# MCU_Build.net
KiCad netlist of a schematic drawn in Altium Designer
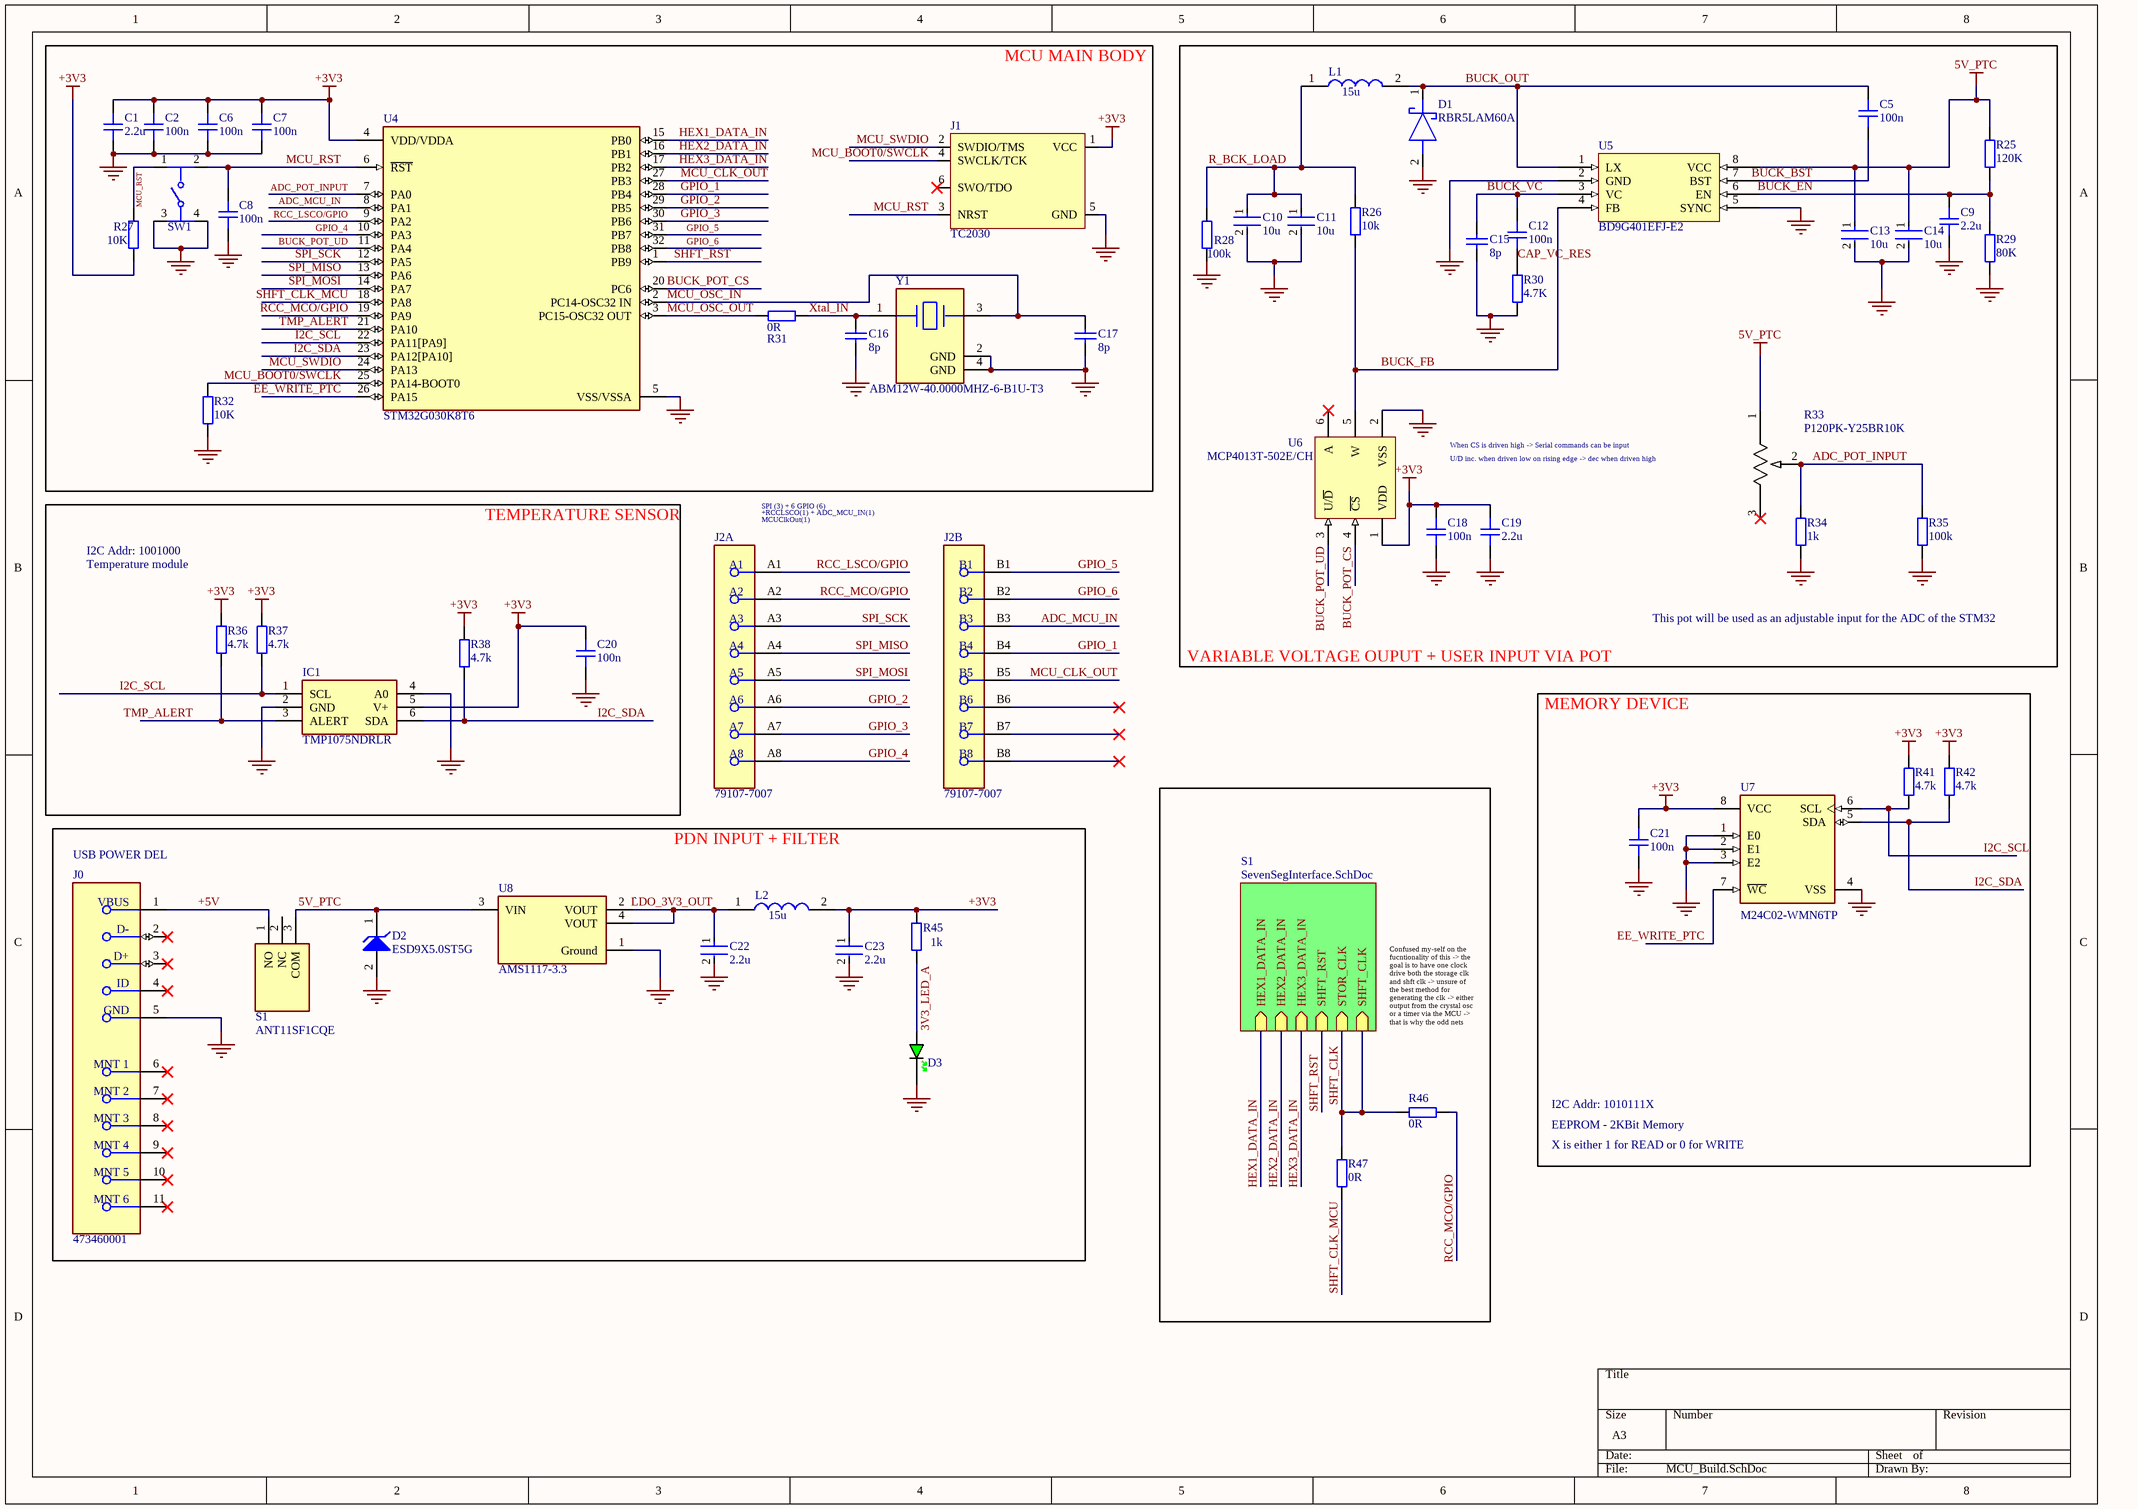
[diagram p0: MCU_Build.SchDoc]

(export (version "E")
  (design (tool "Eeschema 10.0.6"))
  (components
    (comp (ref "C1")
      (value "2.2u")
      (footprint "CAP_0603")
      (description "Capacitor SMD 0603")
      (libsource (lib "PhilsLabLib.") (part "CAP_0603"))
    )
    (comp (ref "C2")
      (value "100n")
      (footprint "CAP_0402")
      (description "Capacitor SMD 0402")
      (libsource (lib "PhilsLabLib.") (part "CAP_0402"))
    )
    (comp (ref "C5")
      (value "100n")
      (footprint "CAP_0402")
      (description "Capacitor SMD 0402")
      (libsource (lib "PhilsLabLib.") (part "CAP_0402"))
    )
    (comp (ref "C6")
      (value "100n")
      (footprint "CAP_0402")
      (description "Capacitor SMD 0402")
      (libsource (lib "PhilsLabLib.") (part "CAP_0402"))
    )
    (comp (ref "C7")
      (value "100n")
      (footprint "CAP_0402")
      (description "Capacitor SMD 0402")
      (libsource (lib "PhilsLabLib.") (part "CAP_0402"))
    )
    (comp (ref "C8")
      (value "100n")
      (footprint "CAP_0402")
      (description "Capacitor SMD 0402")
      (libsource (lib "PhilsLabLib.") (part "CAP_0402"))
    )
    (comp (ref "C9")
      (value "2.2u")
      (footprint "CAP_0603")
      (description "Capacitor SMD 0603")
      (libsource (lib "PhilsLabLib.") (part "CAP_0603"))
    )
    (comp (ref "C10")
      (value "10u")
      (footprint "FP-CL31-IPC_B")
      (description "Cap Ceramic 10uF 16V X7R ±10% SMD 1206 +125°C Embossed T/R")
      (fields (field (name "TOLERANCE") "10%"))
      (libsource (lib "Altium Content Vault") (part "b4654b650e69147ec39a6b967a45e02"))
    )
    (comp (ref "C11")
      (value "10u")
      (footprint "FP-CL31-IPC_B")
      (description "Cap Ceramic 10uF 16V X7R ±10% SMD 1206 +125°C Embossed T/R")
      (fields (field (name "TOLERANCE") "10%"))
      (libsource (lib "Altium Content Vault") (part "b4654b650e69147ec39a6b967a45e02"))
    )
    (comp (ref "C12")
      (value "100n")
      (footprint "CAP_0402")
      (description "Capacitor SMD 0402")
      (libsource (lib "PhilsLabLib.") (part "CAP_0402"))
    )
    (comp (ref "C13")
      (value "10u")
      (footprint "FP-CL31-IPC_B")
      (description "Cap Ceramic 10uF 16V X7R ±10% SMD 1206 +125°C Embossed T/R")
      (fields (field (name "TOLERANCE") "10%"))
      (libsource (lib "Altium Content Vault") (part "b4654b650e69147ec39a6b967a45e02"))
    )
    (comp (ref "C14")
      (value "10u")
      (footprint "FP-CL31-IPC_B")
      (description "Cap Ceramic 10uF 16V X7R ±10% SMD 1206 +125°C Embossed T/R")
      (fields (field (name "TOLERANCE") "10%"))
      (libsource (lib "Altium Content Vault") (part "b4654b650e69147ec39a6b967a45e02"))
    )
    (comp (ref "C15")
      (value "8p")
      (footprint "CAPC1005X55X25LL05T10")
      (fields (field (name "PART NUMBER") "GRM1555C1H8R0BA01D") (field (name "MANUFACTURER") "Murata"))
      (libsource (lib "Altium Content Vault") (part "CAP"))
    )
    (comp (ref "C16")
      (value "8p")
      (footprint "CAPC1005X55X25LL05T10")
      (fields (field (name "PART NUMBER") "GRM1555C1H8R0BA01D") (field (name "MANUFACTURER") "Murata"))
      (libsource (lib "Altium Content Vault") (part "CAP"))
    )
    (comp (ref "C17")
      (value "8p")
      (footprint "CAPC1005X55X25LL05T10")
      (fields (field (name "PART NUMBER") "GRM1555C1H8R0BA01D") (field (name "MANUFACTURER") "Murata"))
      (libsource (lib "Altium Content Vault") (part "CAP"))
    )
    (comp (ref "C18")
      (value "100n")
      (footprint "CAP_0402")
      (description "Capacitor SMD 0402")
      (libsource (lib "PhilsLabLib.") (part "CAP_0402"))
    )
    (comp (ref "C19")
      (value "2.2u")
      (footprint "CAP_0603")
      (description "Capacitor SMD 0603")
      (libsource (lib "PhilsLabLib.") (part "CAP_0603"))
    )
    (comp (ref "C20")
      (value "100n")
      (footprint "CAP_0402")
      (description "Capacitor SMD 0402")
      (libsource (lib "PhilsLabLib.") (part "CAP_0402"))
    )
    (comp (ref "C21")
      (value "100n")
      (footprint "CAP_0402")
      (description "Capacitor SMD 0402")
      (libsource (lib "PhilsLabLib.") (part "CAP_0402"))
    )
    (comp (ref "C22")
      (value "2.2u")
      (footprint "FP-CL31-IPC_B")
      (description "Cap Ceramic 10uF 16V X7R ±10% SMD 1206 +125°C Embossed T/R")
      (fields (field (name "TOLERANCE") "10%"))
      (libsource (lib "Altium Content Vault") (part "b4654b650e69147ec39a6b967a45e02"))
    )
    (comp (ref "C23")
      (value "2.2u")
      (footprint "FP-CL31-IPC_B")
      (description "Cap Ceramic 10uF 16V X7R ±10% SMD 1206 +125°C Embossed T/R")
      (fields (field (name "TOLERANCE") "10%"))
      (libsource (lib "Altium Content Vault") (part "b4654b650e69147ec39a6b967a45e02"))
    )
    (comp (ref "D1")
      (value "RBR5LAM60A")
      (footprint "SamacSys:RF071LAM4S")
      (description "Schottky Diode")
      (libsource (lib "*") (part "RBR5LAM60A"))
    )
    (comp (ref "D2")
      (value "ESD9X5.0ST5G")
      (footprint "ONSC-SOD-923-2-514AA-01_V")
      (fields (field (name "MANUFACTURER") "On Semiconductor"))
      (libsource (lib "Altium Content Vault") (part "ONSC-K1A2-2"))
    )
    (comp (ref "D3")
      (value "GREEN")
      (footprint "LED_0805_GREEN")
      (description "LED 0805 GREEN SMD")
      (libsource (lib "PhilsLabLib.") (part "LED_0805_GREEN"))
    )
    (comp (ref "IC1")
      (value "TMP1075NDRLR")
      (footprint "SamacSys:SOTFL50P160X60-6N")
      (description "Integrated Circuit")
      (fields (field (name "MOUSER PART NUMBER") "595-TMP1075NDRLR"))
      (libsource (lib "*") (part "TMP1075NDRLR"))
    )
    (comp (ref "J0")
      (value "473460001")
      (footprint "FP-473460001-MFG")
      (description "CONN RCPT USB2.0 MICRO B SMD R/A")
      (fields
        (field (name "OCTOPART") "https://octopart.com/47346-0001-molex-7164928")
        (field (name "MANUFACTURER") "Molex")
      )
      (libsource (lib "Altium Content Vault") (part "53ae1f1d9b557310b43ca686e5bb76a"))
    )
    (comp (ref "J1")
      (value "TC2030")
      (footprint "TC2030-FP")
      (description "Tag-Connect No-Solder SWD Debug Connector DO NOT PLACE")
      (fields
        (field (name "MANUFACTURER") "Tag-Connect")
        (field (name "SOURCE") "Schematic-Lib-PhilsLab.SchLib")
      )
      (libsource (lib "Combat Craft") (part "TC2030-NL"))
    )
    (comp (ref "J2")
      (value "79107-7007")
      (footprint "FP-79107-7007-MFG")
      (description "79107-7007 Conn Socket Strip RCP 16 POS 2mm Solder ST Top Entry Thru-Hole Milli-Grid™ Tube")
      (libsource (lib "Altium Content Vault") (part "e4086e6498c21784c506770357dad61"))
    )
    (comp (ref "L1")
      (value "15u")
      (footprint "SamacSys:ASPI-4030S")
      (description "Inductor")
      (fields
        (field (name "MANUFACTURER_PART_NUMBER") "ASPI-4030S-150M-T")
        (field (name "MOUSER PART NUMBER") "815-ASPI-4030S-150MT")
      )
      (libsource (lib "*") (part "ASPI-4030S-150M-T"))
    )
    (comp (ref "L2")
      (value "15u")
      (footprint "SamacSys:ASPI-4030S")
      (description "Inductor")
      (fields
        (field (name "MANUFACTURER_PART_NUMBER") "ASPI-4030S-150M-T")
        (field (name "MOUSER PART NUMBER") "815-ASPI-4030S-150MT")
      )
      (libsource (lib "*") (part "ASPI-4030S-150M-T"))
    )
    (comp (ref "R25")
      (value "120K")
      (footprint "RES_0402")
      (description "Resistor SMD 0402")
      (libsource (lib "PhilsLabLib.") (part "RES_0402"))
    )
    (comp (ref "R26")
      (value "10k")
      (footprint "RES_0402")
      (description "Resistor SMD 0402")
      (libsource (lib "PhilsLabLib.") (part "RES_0402"))
    )
    (comp (ref "R27")
      (value "10K")
      (footprint "RES_0402")
      (description "Resistor SMD 0402")
      (libsource (lib "PhilsLabLib.") (part "RES_0402"))
    )
    (comp (ref "R28")
      (value "100k")
      (footprint "RES_0402")
      (description "Resistor SMD 0402")
      (libsource (lib "PhilsLabLib.") (part "RES_0402"))
    )
    (comp (ref "R29")
      (value "80K")
      (footprint "RES_0402")
      (description "Resistor SMD 0402")
      (libsource (lib "PhilsLabLib.") (part "RES_0402"))
    )
    (comp (ref "R30")
      (value "4.7K")
      (footprint "RES_0402")
      (description "Resistor SMD 0402")
      (libsource (lib "PhilsLabLib.") (part "RES_0402"))
    )
    (comp (ref "R31")
      (value "0R")
      (footprint "RES_0402")
      (description "Resistor SMD 0402")
      (libsource (lib "PhilsLabLib.") (part "RES_0402"))
    )
    (comp (ref "R32")
      (value "10K")
      (footprint "RES_0402")
      (description "Resistor SMD 0402")
      (libsource (lib "PhilsLabLib.") (part "RES_0402"))
    )
    (comp (ref "R33")
      (value "P120PK-Y25BR10K")
      (footprint "POT_P120PK-x25_TTE")
      (description "https://www.digikey.ca/en/products/detail/tt-electronics-bi/P120PK-Y25BR10K/5957454")
      (libsource (lib "P120PK-Y25BR10K") (part "P120PK-Y25BR10K"))
    )
    (comp (ref "R34")
      (value "1k")
      (footprint "RES_0402")
      (description "Resistor SMD 0402")
      (libsource (lib "PhilsLabLib.") (part "RES_0402"))
    )
    (comp (ref "R35")
      (value "100k")
      (footprint "RES_0402")
      (description "Resistor SMD 0402")
      (libsource (lib "PhilsLabLib.") (part "RES_0402"))
    )
    (comp (ref "R36")
      (value "4.7k")
      (footprint "RES_0402")
      (description "Resistor SMD 0402")
      (libsource (lib "PhilsLabLib.") (part "RES_0402"))
    )
    (comp (ref "R37")
      (value "4.7k")
      (footprint "RES_0402")
      (description "Resistor SMD 0402")
      (libsource (lib "PhilsLabLib.") (part "RES_0402"))
    )
    (comp (ref "R38")
      (value "4.7k")
      (footprint "RES_0402")
      (description "Resistor SMD 0402")
      (libsource (lib "PhilsLabLib.") (part "RES_0402"))
    )
    (comp (ref "R41")
      (value "4.7k")
      (footprint "RES_0402")
      (description "Resistor SMD 0402")
      (libsource (lib "PhilsLabLib.") (part "RES_0402"))
    )
    (comp (ref "R42")
      (value "4.7k")
      (footprint "RES_0402")
      (description "Resistor SMD 0402")
      (libsource (lib "PhilsLabLib.") (part "RES_0402"))
    )
    (comp (ref "R45")
      (value "1k")
      (footprint "RES_0402")
      (description "Resistor SMD 0402")
      (libsource (lib "PhilsLabLib.") (part "RES_0402"))
    )
    (comp (ref "R46")
      (value "0R")
      (footprint "RES_0402")
      (description "Resistor SMD 0402")
      (libsource (lib "PhilsLabLib.") (part "RES_0402"))
    )
    (comp (ref "R47")
      (value "0R")
      (footprint "RES_0402")
      (description "Resistor SMD 0402")
      (libsource (lib "PhilsLabLib.") (part "RES_0402"))
    )
    (comp (ref "S1")
      (value "ANT11SF1CQE")
      (footprint "SamacSys:ANT11SF1CQE")
      (description "Switch")
      (libsource (lib "*") (part "ANT11SF1CQE"))
    )
    (comp (ref "SW1")
      (value "PTS810SJM250SMTRLFS")
      (footprint "FP-PTS810SJM250SMTRLFS-MFG")
      (description "SWITCH TACTILE SPST-NO 0.05A 16V")
      (libsource (lib "Altium Content Vault") (part "1adf0dd01260c80cf25a44bfd6b99ba"))
    )
    (comp (ref "U4")
      (value "STM32G030K8T6")
      (footprint "FP-LQFP32-5V-IPC_A")
      (description "IC MCU 32BIT 64KB FLASH 32LQFP")
      (libsource (lib "Altium Content Vault") (part "fea91388a178aa646681c81fcef9c35"))
    )
    (comp (ref "U5")
      (value "BD9G401EFJ-E2")
      (footprint "custom_footprints:SOIC127P600X100_HS-9N")
      (libsource (lib "custom_symbols") (part "BD9G401EFJ-E2"))
    )
    (comp (ref "U6")
      (value "MCP4013T-502E/CH")
      (footprint "SOT-23-CH6_N")
      (description "Low-Cost 64-Step Volatile Digital POT, 6-Pin SOT-23, Extended Temperature, Tape and Reel")
      (libsource (lib "Altium Content Vault") (part "IN-DPOT-MCP4012-6"))
    )
    (comp (ref "U7")
      (value "M24C02-WMN6TP")
      (footprint "FP-SO8N-SO-A-MFG")
      (description "IC EEPROM 2K I2C 400KHZ 8SO")
      (fields
        (field (name "MANUFACTURER") "STMicroelectronics")
        (field (name "OCTOPART") "https://octopart.com/m24c02-wmn6tp-stmicroelectronics-55404516")
      )
      (libsource (lib "Altium Content Vault") (part "6c91e1c1613830ec3abd94c18390ae3"))
    )
    (comp (ref "U8")
      (value "AMS1117-3.3")
      (footprint "FP-AMS1117-IPC_C")
      (description "LDO Voltage Regulators 1A, 3.3V")
      (fields
        (field (name "OCTOPART") "https://octopart.com/ams1117-3.3-advanced+monolithic+systems-25899300")
        (field (name "MANUFACTURER") "Advanced Monolithic Systems")
      )
      (libsource (lib "Altium Content Vault") (part "8bdbb5f8e77002000e30dd2845d0354"))
    )
    (comp (ref "Y1")
      (value "ABM12W-40.0000MHZ-6-B1U-T3")
      (footprint "FP-ABM12W-MFG")
      (description "Crystal 40MHz ±10ppm 6pF SMD-4 1.6mm x 1.2mm")
      (libsource (lib "Altium Content Vault") (part "7e21b6506f3e6571bf1303cf0e4723c"))
    )
  )
  (nets
    (net (code "1") (name "+3V3") (class "Default")
      (node (ref "C1") (pin "2") (pinfunction "2_2") (pintype "passive"))
      (node (ref "C18") (pin "2") (pinfunction "2_2") (pintype "passive"))
      (node (ref "C19") (pin "2") (pinfunction "2_2") (pintype "passive"))
      (node (ref "C2") (pin "2") (pinfunction "2_2") (pintype "passive"))
      (node (ref "C20") (pin "2") (pinfunction "2_2") (pintype "passive"))
      (node (ref "C21") (pin "2") (pinfunction "2_2") (pintype "passive"))
      (node (ref "C23") (pin "1") (pinfunction "1_1") (pintype "passive"))
      (node (ref "C6") (pin "2") (pinfunction "2_2") (pintype "passive"))
      (node (ref "C7") (pin "2") (pinfunction "2_2") (pintype "passive"))
      (node (ref "IC1") (pin "5") (pinfunction "V+_5") (pintype "passive"))
      (node (ref "J1") (pin "1") (pinfunction "VCC_1") (pintype "passive"))
      (node (ref "L2") (pin "2") (pinfunction "2_2") (pintype "passive"))
      (node (ref "R27") (pin "2") (pinfunction "2_2") (pintype "passive"))
      (node (ref "R36") (pin "1") (pinfunction "1_1") (pintype "passive"))
      (node (ref "R37") (pin "1") (pinfunction "1_1") (pintype "passive"))
      (node (ref "R38") (pin "1") (pinfunction "1_1") (pintype "passive"))
      (node (ref "R41") (pin "1") (pinfunction "1_1") (pintype "passive"))
      (node (ref "R42") (pin "1") (pinfunction "1_1") (pintype "passive"))
      (node (ref "R45") (pin "1") (pinfunction "1_1") (pintype "passive"))
      (node (ref "U4") (pin "4") (pinfunction "VDD/VDDA_4") (pintype "power_in"))
      (node (ref "U6") (pin "1") (pinfunction "VDD_1") (pintype "power_in"))
      (node (ref "U7") (pin "8") (pinfunction "VCC_8") (pintype "power_in"))
    )
    (net (code "2") (name "/+5V") (class "Default")
      (node (ref "J0") (pin "1") (pinfunction "VBUS_1") (pintype "power_in"))
      (node (ref "S1") (pin "1") (pinfunction "NO_1") (pintype "passive"))
    )
    (net (code "3") (name "/3V3_LED_A") (class "Default")
      (node (ref "D3") (pin "A") (pinfunction "A_A") (pintype "passive"))
      (node (ref "R45") (pin "2") (pinfunction "2_2") (pintype "passive"))
    )
    (net (code "4") (name "/ADC_MCU_IN") (class "Default")
      (node (ref "J2") (pin "B3") (pinfunction "B3_B3") (pintype "passive"))
      (node (ref "U4") (pin "8") (pinfunction "PA1_8") (pintype "bidirectional"))
    )
    (net (code "5") (name "/ADC_POT_INPUT") (class "Default")
      (node (ref "R33") (pin "2") (pinfunction "2_2") (pintype "passive"))
      (node (ref "R34") (pin "2") (pinfunction "2_2") (pintype "passive"))
      (node (ref "R35") (pin "2") (pinfunction "2_2") (pintype "passive"))
      (node (ref "U4") (pin "7") (pinfunction "PA0_7") (pintype "bidirectional"))
    )
    (net (code "6") (name "/BUCK_BST") (class "Default")
      (node (ref "C5") (pin "1") (pinfunction "1_1") (pintype "passive"))
      (node (ref "U5") (pin "7") (pinfunction "BST_7") (pintype "input"))
    )
    (net (code "7") (name "/BUCK_EN") (class "Default")
      (node (ref "C9") (pin "2") (pinfunction "2_2") (pintype "passive"))
      (node (ref "R25") (pin "1") (pinfunction "1_1") (pintype "passive"))
      (node (ref "R29") (pin "2") (pinfunction "2_2") (pintype "passive"))
      (node (ref "U5") (pin "6") (pinfunction "EN_6") (pintype "input"))
    )
    (net (code "8") (name "/BUCK_FB") (class "Default")
      (node (ref "R26") (pin "1") (pinfunction "1_1") (pintype "passive"))
      (node (ref "U5") (pin "4") (pinfunction "FB_4") (pintype "input"))
      (node (ref "U6") (pin "5") (pinfunction "W_5") (pintype "passive"))
    )
    (net (code "9") (name "/BUCK_OUT") (class "Default")
      (node (ref "C5") (pin "2") (pinfunction "2_2") (pintype "passive"))
      (node (ref "D1") (pin "1") (pinfunction "K_1") (pintype "passive"))
      (node (ref "L1") (pin "2") (pinfunction "2_2") (pintype "passive"))
      (node (ref "U5") (pin "1") (pinfunction "LX_1") (pintype "input"))
    )
    (net (code "10") (name "/BUCK_POT_CS") (class "Default")
      (node (ref "U4") (pin "20") (pinfunction "PC6_20") (pintype "bidirectional"))
      (node (ref "U6") (pin "4") (pinfunction "~{CS}_4") (pintype "input"))
    )
    (net (code "11") (name "/BUCK_POT_UD") (class "Default")
      (node (ref "U4") (pin "11") (pinfunction "PA4_11") (pintype "bidirectional"))
      (node (ref "U6") (pin "3") (pinfunction "U/~{D}_3") (pintype "input"))
    )
    (net (code "12") (name "/BUCK_VC") (class "Default")
      (node (ref "C12") (pin "2") (pinfunction "2_2") (pintype "passive"))
      (node (ref "C15") (pin "2") (pinfunction "2_2") (pintype "passive"))
      (node (ref "U5") (pin "3") (pinfunction "VC_3") (pintype "input"))
    )
    (net (code "13") (name "/CAP_VC_RES") (class "Default")
      (node (ref "C12") (pin "1") (pinfunction "1_1") (pintype "passive"))
      (node (ref "R30") (pin "2") (pinfunction "2_2") (pintype "passive"))
    )
    (net (code "14") (name "/EE_WRITE_PTC") (class "Default")
      (node (ref "U4") (pin "26") (pinfunction "PA15_26") (pintype "bidirectional"))
      (node (ref "U7") (pin "7") (pinfunction "~{WC}_7") (pintype "input"))
    )
    (net (code "15") (name "/GPIO_1") (class "Default")
      (node (ref "J2") (pin "B4") (pinfunction "B4_B4") (pintype "passive"))
      (node (ref "U4") (pin "28") (pinfunction "PB4_28") (pintype "bidirectional"))
    )
    (net (code "16") (name "/GPIO_2") (class "Default")
      (node (ref "J2") (pin "A6") (pinfunction "A6_A6") (pintype "passive"))
      (node (ref "U4") (pin "29") (pinfunction "PB5_29") (pintype "bidirectional"))
    )
    (net (code "17") (name "/GPIO_3") (class "Default")
      (node (ref "J2") (pin "A7") (pinfunction "A7_A7") (pintype "passive"))
      (node (ref "U4") (pin "30") (pinfunction "PB6_30") (pintype "bidirectional"))
    )
    (net (code "18") (name "/GPIO_4") (class "Default")
      (node (ref "J2") (pin "A8") (pinfunction "A8_A8") (pintype "passive"))
      (node (ref "U4") (pin "10") (pinfunction "PA3_10") (pintype "bidirectional"))
    )
    (net (code "19") (name "/GPIO_5") (class "Default")
      (node (ref "J2") (pin "B1") (pinfunction "B1_B1") (pintype "passive"))
      (node (ref "U4") (pin "31") (pinfunction "PB7_31") (pintype "bidirectional"))
    )
    (net (code "20") (name "/GPIO_6") (class "Default")
      (node (ref "J2") (pin "B2") (pinfunction "B2_B2") (pintype "passive"))
      (node (ref "U4") (pin "32") (pinfunction "PB8_32") (pintype "bidirectional"))
    )
    (net (code "21") (name "/HEX1_DATA_IN") (class "Default")
      (node (ref "U4") (pin "15") (pinfunction "PB0_15") (pintype "bidirectional"))
    )
    (net (code "22") (name "/HEX2_DATA_IN") (class "Default")
      (node (ref "U4") (pin "16") (pinfunction "PB1_16") (pintype "bidirectional"))
    )
    (net (code "23") (name "/HEX3_DATA_IN") (class "Default")
      (node (ref "U4") (pin "17") (pinfunction "PB2_17") (pintype "bidirectional"))
    )
    (net (code "24") (name "/I2C_SCL") (class "Default")
      (node (ref "IC1") (pin "1") (pinfunction "SCL_1") (pintype "passive"))
      (node (ref "R37") (pin "2") (pinfunction "2_2") (pintype "passive"))
      (node (ref "R41") (pin "2") (pinfunction "2_2") (pintype "passive"))
      (node (ref "U4") (pin "22") (pinfunction "PA11[PA9]_22") (pintype "bidirectional"))
      (node (ref "U7") (pin "6") (pinfunction "SCL_6") (pintype "input"))
    )
    (net (code "25") (name "/I2C_SDA") (class "Default")
      (node (ref "IC1") (pin "6") (pinfunction "SDA_6") (pintype "passive"))
      (node (ref "R38") (pin "2") (pinfunction "2_2") (pintype "passive"))
      (node (ref "R42") (pin "2") (pinfunction "2_2") (pintype "passive"))
      (node (ref "U4") (pin "23") (pinfunction "PA12[PA10]_23") (pintype "bidirectional"))
      (node (ref "U7") (pin "5") (pinfunction "SDA_5") (pintype "bidirectional"))
    )
    (net (code "26") (name "/LDO_3V3_OUT") (class "Default")
      (node (ref "C22") (pin "1") (pinfunction "1_1") (pintype "passive"))
      (node (ref "L2") (pin "1") (pinfunction "1_1") (pintype "passive"))
      (node (ref "U8") (pin "2") (pinfunction "VOUT_2") (pintype "passive"))
      (node (ref "U8") (pin "4") (pinfunction "VOUT_4") (pintype "passive"))
    )
    (net (code "27") (name "/MCU_BOOT0{slash}SWCLK") (class "Default")
      (node (ref "J1") (pin "4") (pinfunction "SWCLK/TCK_4") (pintype "passive"))
      (node (ref "R32") (pin "1") (pinfunction "1_1") (pintype "passive"))
      (node (ref "U4") (pin "25") (pinfunction "PA14-BOOT0_25") (pintype "bidirectional"))
    )
    (net (code "28") (name "/MCU_CLK_OUT") (class "Default")
      (node (ref "J2") (pin "B5") (pinfunction "B5_B5") (pintype "passive"))
      (node (ref "U4") (pin "27") (pinfunction "PB3_27") (pintype "bidirectional"))
    )
    (net (code "29") (name "/MCU_OSC_IN") (class "Default")
      (node (ref "C17") (pin "2") (pinfunction "2_2") (pintype "passive"))
      (node (ref "U4") (pin "2") (pinfunction "PC14-OSC32_IN_2") (pintype "bidirectional"))
      (node (ref "Y1") (pin "3") (pinfunction "3_3") (pintype "passive"))
    )
    (net (code "30") (name "/MCU_OSC_OUT") (class "Default")
      (node (ref "R31") (pin "2") (pinfunction "2_2") (pintype "passive"))
      (node (ref "U4") (pin "3") (pinfunction "PC15-OSC32_OUT_3") (pintype "bidirectional"))
    )
    (net (code "31") (name "/MCU_RST") (class "Default")
      (node (ref "C8") (pin "2") (pinfunction "2_2") (pintype "passive"))
      (node (ref "J1") (pin "3") (pinfunction "NRST_3") (pintype "passive"))
      (node (ref "R27") (pin "1") (pinfunction "1_1") (pintype "passive"))
      (node (ref "SW1") (pin "1") (pinfunction "1_1") (pintype "passive"))
      (node (ref "SW1") (pin "2") (pinfunction "2_2") (pintype "passive"))
      (node (ref "U4") (pin "6") (pinfunction "~{RST}_6") (pintype "input"))
    )
    (net (code "32") (name "/MCU_SWDIO") (class "Default")
      (node (ref "J1") (pin "2") (pinfunction "SWDIO/TMS_2") (pintype "passive"))
      (node (ref "U4") (pin "24") (pinfunction "PA13_24") (pintype "bidirectional"))
    )
    (net (code "33") (name "/RCC_LSCO{slash}GPIO") (class "Default")
      (node (ref "J2") (pin "A1") (pinfunction "A1_A1") (pintype "passive"))
      (node (ref "U4") (pin "9") (pinfunction "PA2_9") (pintype "bidirectional"))
    )
    (net (code "34") (name "/RCC_MCO{slash}GPIO") (class "Default")
      (node (ref "J2") (pin "A2") (pinfunction "A2_A2") (pintype "passive"))
      (node (ref "R46") (pin "1") (pinfunction "1_1") (pintype "passive"))
      (node (ref "U4") (pin "19") (pinfunction "PA9_19") (pintype "bidirectional"))
    )
    (net (code "35") (name "/R_BCK_LOAD") (class "Default")
      (node (ref "C10") (pin "1") (pinfunction "1_1") (pintype "passive"))
      (node (ref "C11") (pin "1") (pinfunction "1_1") (pintype "passive"))
      (node (ref "L1") (pin "1") (pinfunction "1_1") (pintype "passive"))
      (node (ref "R26") (pin "2") (pinfunction "2_2") (pintype "passive"))
      (node (ref "R28") (pin "2") (pinfunction "2_2") (pintype "passive"))
    )
    (net (code "36") (name "/SHFT_CLK") (class "Default")
      (node (ref "R46") (pin "2") (pinfunction "2_2") (pintype "passive"))
      (node (ref "R47") (pin "1") (pinfunction "1_1") (pintype "passive"))
    )
    (net (code "37") (name "/SHFT_CLK_MCU") (class "Default")
      (node (ref "R47") (pin "2") (pinfunction "2_2") (pintype "passive"))
      (node (ref "U4") (pin "18") (pinfunction "PA8_18") (pintype "bidirectional"))
    )
    (net (code "38") (name "/SHFT_RST") (class "Default")
      (node (ref "U4") (pin "1") (pinfunction "PB9_1") (pintype "bidirectional"))
    )
    (net (code "39") (name "/SPI_MISO") (class "Default")
      (node (ref "J2") (pin "A4") (pinfunction "A4_A4") (pintype "passive"))
      (node (ref "U4") (pin "13") (pinfunction "PA6_13") (pintype "bidirectional"))
    )
    (net (code "40") (name "/SPI_MOSI") (class "Default")
      (node (ref "J2") (pin "A5") (pinfunction "A5_A5") (pintype "passive"))
      (node (ref "U4") (pin "14") (pinfunction "PA7_14") (pintype "bidirectional"))
    )
    (net (code "41") (name "/SPI_SCK") (class "Default")
      (node (ref "J2") (pin "A3") (pinfunction "A3_A3") (pintype "passive"))
      (node (ref "U4") (pin "12") (pinfunction "PA5_12") (pintype "bidirectional"))
    )
    (net (code "42") (name "/TMP_ALERT") (class "Default")
      (node (ref "IC1") (pin "3") (pinfunction "ALERT_3") (pintype "passive"))
      (node (ref "R36") (pin "2") (pinfunction "2_2") (pintype "passive"))
      (node (ref "U4") (pin "21") (pinfunction "PA10_21") (pintype "bidirectional"))
    )
    (net (code "43") (name "/Xtal_IN") (class "Default")
      (node (ref "C16") (pin "2") (pinfunction "2_2") (pintype "passive"))
      (node (ref "R31") (pin "1") (pinfunction "1_1") (pintype "passive"))
      (node (ref "Y1") (pin "1") (pinfunction "1_1") (pintype "passive"))
    )
    (net (code "44") (name "5V_PTC") (class "Default")
      (node (ref "C13") (pin "1") (pinfunction "1_1") (pintype "passive"))
      (node (ref "C14") (pin "1") (pinfunction "1_1") (pintype "passive"))
      (node (ref "D2") (pin "1") (pinfunction "K_1") (pintype "passive"))
      (node (ref "R25") (pin "2") (pinfunction "2_2") (pintype "passive"))
      (node (ref "R33") (pin "1") (pinfunction "1_1") (pintype "passive"))
      (node (ref "S1") (pin "3") (pinfunction "COM_3") (pintype "passive"))
      (node (ref "U5") (pin "8") (pinfunction "VCC_8") (pintype "input"))
      (node (ref "U8") (pin "3") (pinfunction "VIN_3") (pintype "power_in"))
    )
    (net (code "45") (name "GND") (class "Default")
      (node (ref "C1") (pin "1") (pinfunction "1_1") (pintype "passive"))
      (node (ref "C10") (pin "2") (pinfunction "2_2") (pintype "passive"))
      (node (ref "C11") (pin "2") (pinfunction "2_2") (pintype "passive"))
      (node (ref "C13") (pin "2") (pinfunction "2_2") (pintype "passive"))
      (node (ref "C14") (pin "2") (pinfunction "2_2") (pintype "passive"))
      (node (ref "C15") (pin "1") (pinfunction "1_1") (pintype "passive"))
      (node (ref "C16") (pin "1") (pinfunction "1_1") (pintype "passive"))
      (node (ref "C17") (pin "1") (pinfunction "1_1") (pintype "passive"))
      (node (ref "C18") (pin "1") (pinfunction "1_1") (pintype "passive"))
      (node (ref "C19") (pin "1") (pinfunction "1_1") (pintype "passive"))
      (node (ref "C2") (pin "1") (pinfunction "1_1") (pintype "passive"))
      (node (ref "C20") (pin "1") (pinfunction "1_1") (pintype "passive"))
      (node (ref "C21") (pin "1") (pinfunction "1_1") (pintype "passive"))
      (node (ref "C22") (pin "2") (pinfunction "2_2") (pintype "passive"))
      (node (ref "C23") (pin "2") (pinfunction "2_2") (pintype "passive"))
      (node (ref "C6") (pin "1") (pinfunction "1_1") (pintype "passive"))
      (node (ref "C7") (pin "1") (pinfunction "1_1") (pintype "passive"))
      (node (ref "C8") (pin "1") (pinfunction "1_1") (pintype "passive"))
      (node (ref "C9") (pin "1") (pinfunction "1_1") (pintype "passive"))
      (node (ref "D1") (pin "2") (pinfunction "A_2") (pintype "passive"))
      (node (ref "D2") (pin "2") (pinfunction "A_2") (pintype "passive"))
      (node (ref "D3") (pin "K") (pinfunction "K_K") (pintype "passive"))
      (node (ref "IC1") (pin "2") (pinfunction "GND_2") (pintype "passive"))
      (node (ref "IC1") (pin "4") (pinfunction "A0_4") (pintype "passive"))
      (node (ref "J0") (pin "5") (pinfunction "GND_5") (pintype "power_in"))
      (node (ref "J1") (pin "5") (pinfunction "GND_5") (pintype "passive"))
      (node (ref "R28") (pin "1") (pinfunction "1_1") (pintype "passive"))
      (node (ref "R29") (pin "1") (pinfunction "1_1") (pintype "passive"))
      (node (ref "R30") (pin "1") (pinfunction "1_1") (pintype "passive"))
      (node (ref "R32") (pin "2") (pinfunction "2_2") (pintype "passive"))
      (node (ref "R34") (pin "1") (pinfunction "1_1") (pintype "passive"))
      (node (ref "R35") (pin "1") (pinfunction "1_1") (pintype "passive"))
      (node (ref "SW1") (pin "3") (pinfunction "3_3") (pintype "passive"))
      (node (ref "SW1") (pin "4") (pinfunction "4_4") (pintype "passive"))
      (node (ref "U4") (pin "5") (pinfunction "VSS/VSSA_5") (pintype "power_in"))
      (node (ref "U5") (pin "2") (pinfunction "GND_2") (pintype "input"))
      (node (ref "U5") (pin "5") (pinfunction "SYNC_5") (pintype "input"))
      (node (ref "U6") (pin "2") (pinfunction "VSS_2") (pintype "power_in"))
      (node (ref "U7") (pin "1") (pinfunction "E0_1") (pintype "input"))
      (node (ref "U7") (pin "2") (pinfunction "E1_2") (pintype "input"))
      (node (ref "U7") (pin "3") (pinfunction "E2_3") (pintype "input"))
      (node (ref "U7") (pin "4") (pinfunction "VSS_4") (pintype "power_in"))
      (node (ref "U8") (pin "1") (pinfunction "Ground_1") (pintype "power_in"))
      (node (ref "Y1") (pin "2") (pinfunction "GND_2") (pintype "power_in"))
      (node (ref "Y1") (pin "4") (pinfunction "GND_4") (pintype "power_in"))
    )
    (net (code "46") (name "unconnected-(J0-D+-Pad3)") (class "Default")
      (node (ref "J0") (pin "3") (pinfunction "D+_3") (pintype "bidirectional+no_connect"))
    )
    (net (code "47") (name "unconnected-(J0-D--Pad2)") (class "Default")
      (node (ref "J0") (pin "2") (pinfunction "D-_2") (pintype "bidirectional+no_connect"))
    )
    (net (code "48") (name "unconnected-(J0-ID-Pad4)") (class "Default")
      (node (ref "J0") (pin "4") (pinfunction "ID_4") (pintype "passive+no_connect"))
    )
    (net (code "49") (name "unconnected-(J0-MNT_1-Pad6)") (class "Default")
      (node (ref "J0") (pin "6") (pinfunction "MNT_1_6") (pintype "passive+no_connect"))
    )
    (net (code "50") (name "unconnected-(J0-MNT_2-Pad7)") (class "Default")
      (node (ref "J0") (pin "7") (pinfunction "MNT_2_7") (pintype "passive+no_connect"))
    )
    (net (code "51") (name "unconnected-(J0-MNT_3-Pad8)") (class "Default")
      (node (ref "J0") (pin "8") (pinfunction "MNT_3_8") (pintype "passive+no_connect"))
    )
    (net (code "52") (name "unconnected-(J0-MNT_4-Pad9)") (class "Default")
      (node (ref "J0") (pin "9") (pinfunction "MNT_4_9") (pintype "passive+no_connect"))
    )
    (net (code "53") (name "unconnected-(J0-MNT_5-Pad10)") (class "Default")
      (node (ref "J0") (pin "10") (pinfunction "MNT_5_10") (pintype "passive+no_connect"))
    )
    (net (code "54") (name "unconnected-(J0-MNT_6-Pad11)") (class "Default")
      (node (ref "J0") (pin "11") (pinfunction "MNT_6_11") (pintype "passive+no_connect"))
    )
    (net (code "55") (name "unconnected-(J1-SWO{slash}TDO-Pad6)") (class "Default")
      (node (ref "J1") (pin "6") (pinfunction "SWO/TDO_6") (pintype "passive+no_connect"))
    )
    (net (code "56") (name "unconnected-(J2-PadB6)") (class "Default")
      (node (ref "J2") (pin "B6") (pinfunction "B6_B6") (pintype "passive+no_connect"))
    )
    (net (code "57") (name "unconnected-(J2-PadB7)") (class "Default")
      (node (ref "J2") (pin "B7") (pinfunction "B7_B7") (pintype "passive+no_connect"))
    )
    (net (code "58") (name "unconnected-(J2-PadB8)") (class "Default")
      (node (ref "J2") (pin "B8") (pinfunction "B8_B8") (pintype "passive+no_connect"))
    )
    (net (code "59") (name "unconnected-(R33-Pad3)") (class "Default")
      (node (ref "R33") (pin "3") (pinfunction "3_3") (pintype "passive+no_connect"))
    )
    (net (code "60") (name "unconnected-(S1-NC-Pad2)") (class "Default")
      (node (ref "S1") (pin "2") (pinfunction "NC_2") (pintype "passive"))
    )
    (net (code "61") (name "unconnected-(U6-A-Pad6)") (class "Default")
      (node (ref "U6") (pin "6") (pinfunction "A_6") (pintype "passive+no_connect"))
    )
  )
)
